# backplate.net
KiCad netlist of a schematic drawn in EAGLE
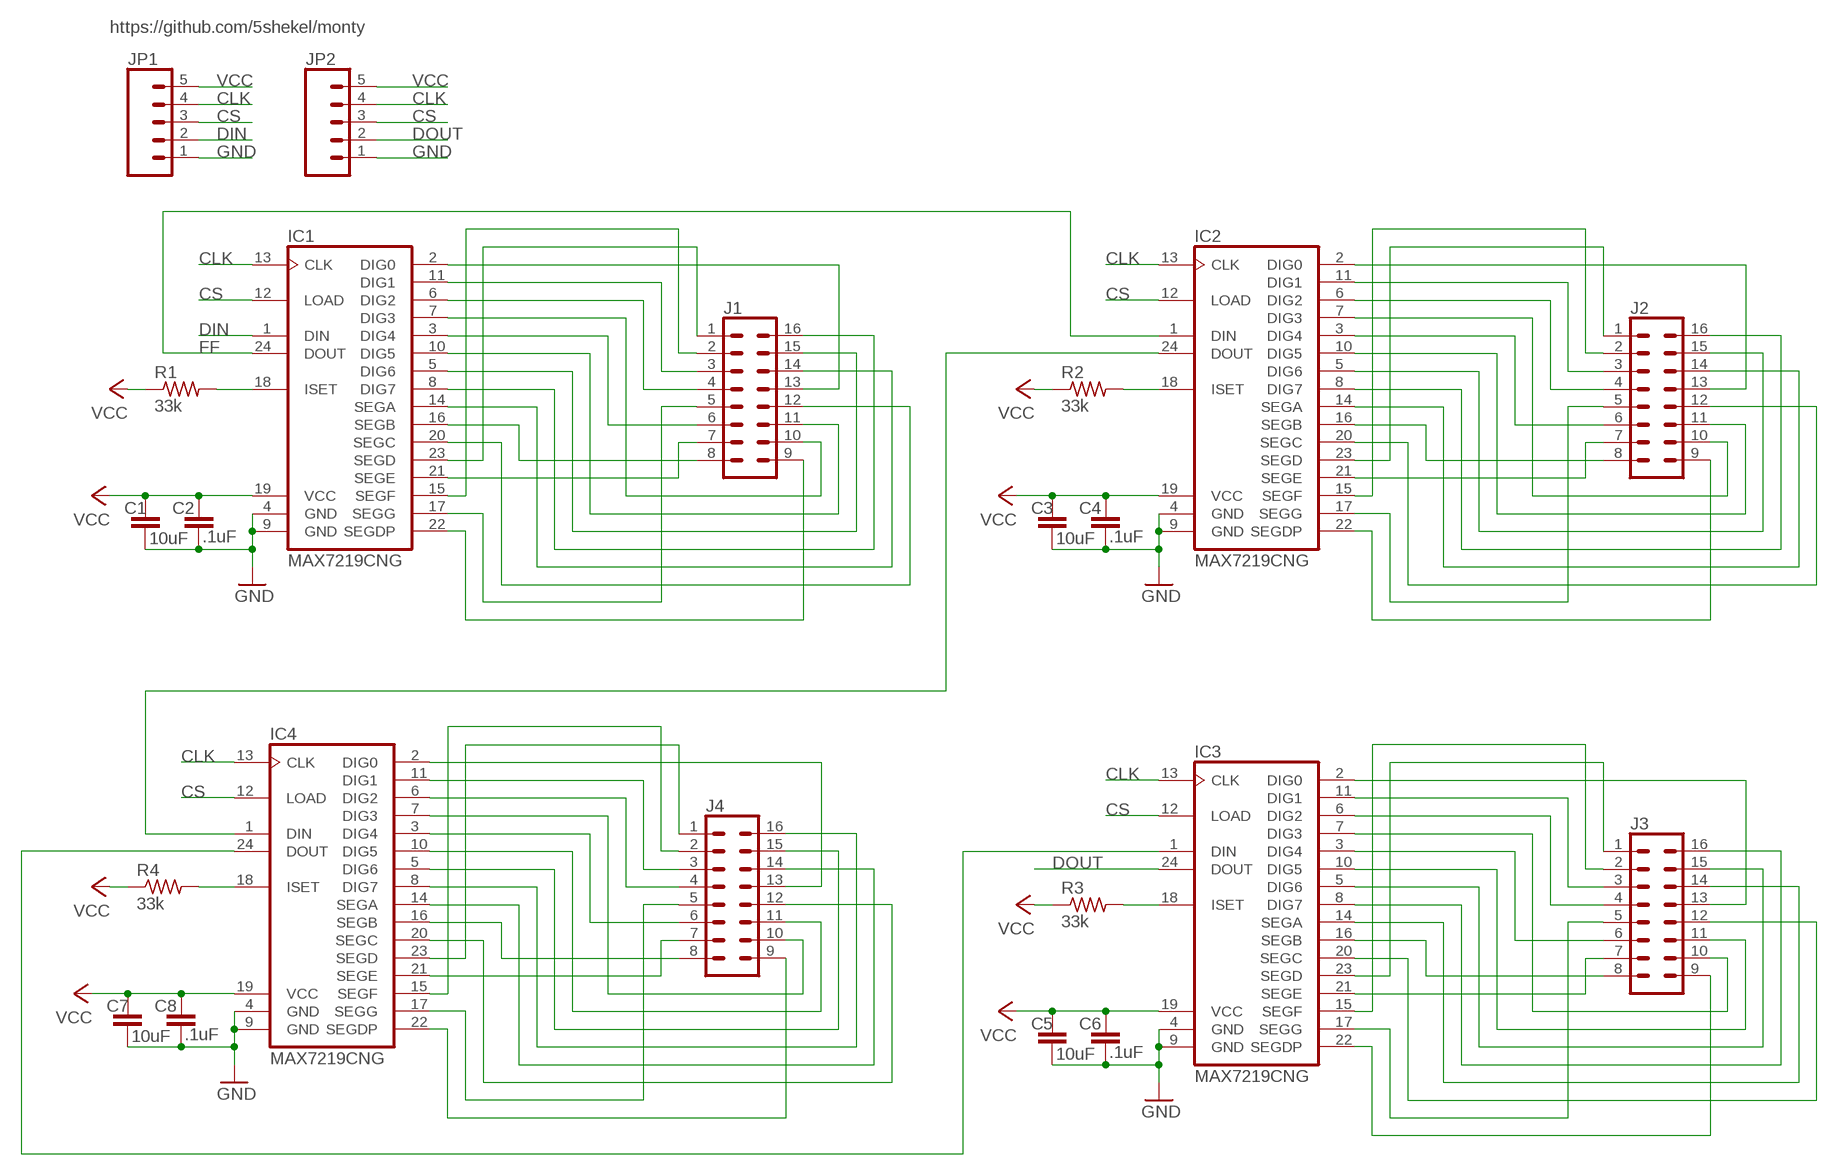
[diagram p0: schematic, sheet 1]

(export (version "E")
  (design (tool "Eeschema 10.0.6"))
  (components
    (comp (ref "C1")
      (value "10uF")
      (footprint "eagle-import:0805")
      (libsource (lib "eagle-import") (part "CAP0805"))
    )
    (comp (ref "C2")
      (value ".1uF")
      (footprint "eagle-import:0805")
      (libsource (lib "eagle-import") (part "CAP0805"))
    )
    (comp (ref "C3")
      (value "10uF")
      (footprint "eagle-import:0805")
      (libsource (lib "eagle-import") (part "CAP0805"))
    )
    (comp (ref "C4")
      (value ".1uF")
      (footprint "eagle-import:0805")
      (libsource (lib "eagle-import") (part "CAP0805"))
    )
    (comp (ref "C5")
      (value "10uF")
      (footprint "eagle-import:0805")
      (libsource (lib "eagle-import") (part "CAP0805"))
    )
    (comp (ref "C6")
      (value ".1uF")
      (footprint "eagle-import:0805")
      (libsource (lib "eagle-import") (part "CAP0805"))
    )
    (comp (ref "C7")
      (value "10uF")
      (footprint "eagle-import:0805")
      (libsource (lib "eagle-import") (part "CAP0805"))
    )
    (comp (ref "C8")
      (value ".1uF")
      (footprint "eagle-import:0805")
      (libsource (lib "eagle-import") (part "CAP0805"))
    )
    (comp (ref "IC1")
      (value "MAX7219CNG")
      (footprint "eagle-import:DIL24-3")
      (fields (field (name "MF") "MAXIM"))
      (libsource (lib "eagle-import") (part "MAX7219CNG"))
    )
    (comp (ref "IC2")
      (value "MAX7219CNG")
      (footprint "eagle-import:DIL24-3")
      (fields (field (name "MF") "MAXIM"))
      (libsource (lib "eagle-import") (part "MAX7219CNG"))
    )
    (comp (ref "IC3")
      (value "MAX7219CNG")
      (footprint "eagle-import:DIL24-3")
      (fields (field (name "MF") "MAXIM"))
      (libsource (lib "eagle-import") (part "MAX7219CNG"))
    )
    (comp (ref "IC4")
      (value "MAX7219CNG")
      (footprint "eagle-import:DIL24-3")
      (fields (field (name "MF") "MAXIM"))
      (libsource (lib "eagle-import") (part "MAX7219CNG"))
    )
    (comp (ref "J1")
      (value "CONN_08X2IC")
      (footprint "eagle-import:2X8")
      (libsource (lib "eagle-import") (part "CONN_08X2IC"))
    )
    (comp (ref "J2")
      (value "CONN_08X2IC")
      (footprint "eagle-import:2X8")
      (libsource (lib "eagle-import") (part "CONN_08X2IC"))
    )
    (comp (ref "J3")
      (value "CONN_08X2IC")
      (footprint "eagle-import:2X8")
      (libsource (lib "eagle-import") (part "CONN_08X2IC"))
    )
    (comp (ref "J4")
      (value "CONN_08X2IC")
      (footprint "eagle-import:2X8")
      (libsource (lib "eagle-import") (part "CONN_08X2IC"))
    )
    (comp (ref "JP1")
      (value "CONN_05")
      (footprint "eagle-import:1X05")
      (libsource (lib "eagle-import") (part "CONN_05"))
    )
    (comp (ref "JP2")
      (value "CONN_05")
      (footprint "eagle-import:1X05")
      (libsource (lib "eagle-import") (part "CONN_05"))
    )
    (comp (ref "R1")
      (value "33k")
      (footprint "eagle-import:V526-0")
      (libsource (lib "eagle-import") (part "R-US_V526-0"))
    )
    (comp (ref "R2")
      (value "33k")
      (footprint "eagle-import:V526-0")
      (libsource (lib "eagle-import") (part "R-US_V526-0"))
    )
    (comp (ref "R3")
      (value "33k")
      (footprint "eagle-import:V526-0")
      (libsource (lib "eagle-import") (part "R-US_V526-0"))
    )
    (comp (ref "R4")
      (value "33k")
      (footprint "eagle-import:V526-0")
      (libsource (lib "eagle-import") (part "R-US_V526-0"))
    )
  )
  (nets
    (net (code "1") (name "/CLK") (class "Default")
      (node (ref "IC1") (pin "13") (pinfunction "CLK_13") (pintype "input"))
      (node (ref "IC2") (pin "13") (pinfunction "CLK_13") (pintype "input"))
      (node (ref "IC3") (pin "13") (pinfunction "CLK_13") (pintype "input"))
      (node (ref "IC4") (pin "13") (pinfunction "CLK_13") (pintype "input"))
      (node (ref "JP1") (pin "4") (pinfunction "4_4") (pintype "passive"))
      (node (ref "JP2") (pin "4") (pinfunction "4_4") (pintype "passive"))
    )
    (net (code "2") (name "/CS") (class "Default")
      (node (ref "IC1") (pin "12") (pinfunction "LOAD_12") (pintype "input"))
      (node (ref "IC2") (pin "12") (pinfunction "LOAD_12") (pintype "input"))
      (node (ref "IC3") (pin "12") (pinfunction "LOAD_12") (pintype "input"))
      (node (ref "IC4") (pin "12") (pinfunction "LOAD_12") (pintype "input"))
      (node (ref "JP1") (pin "3") (pinfunction "3_3") (pintype "passive"))
      (node (ref "JP2") (pin "3") (pinfunction "3_3") (pintype "passive"))
    )
    (net (code "3") (name "/DIN") (class "Default")
      (node (ref "IC1") (pin "1") (pinfunction "DIN_1") (pintype "input"))
      (node (ref "JP1") (pin "2") (pinfunction "2_2") (pintype "passive"))
    )
    (net (code "4") (name "/DOUT") (class "Default")
      (node (ref "IC3") (pin "24") (pinfunction "DOUT_24") (pintype "output"))
      (node (ref "JP2") (pin "2") (pinfunction "2_2") (pintype "passive"))
    )
    (net (code "5") (name "/FF") (class "Default")
      (node (ref "IC1") (pin "24") (pinfunction "DOUT_24") (pintype "output"))
      (node (ref "IC2") (pin "1") (pinfunction "DIN_1") (pintype "input"))
    )
    (net (code "6") (name "GND") (class "Default")
      (node (ref "C1") (pin "2") (pinfunction "2_2") (pintype "passive"))
      (node (ref "C2") (pin "2") (pinfunction "2_2") (pintype "passive"))
      (node (ref "C3") (pin "2") (pinfunction "2_2") (pintype "passive"))
      (node (ref "C4") (pin "2") (pinfunction "2_2") (pintype "passive"))
      (node (ref "C5") (pin "2") (pinfunction "2_2") (pintype "passive"))
      (node (ref "C6") (pin "2") (pinfunction "2_2") (pintype "passive"))
      (node (ref "C7") (pin "2") (pinfunction "2_2") (pintype "passive"))
      (node (ref "C8") (pin "2") (pinfunction "2_2") (pintype "passive"))
      (node (ref "IC1") (pin "4") (pinfunction "GND_4") (pintype "power_in"))
      (node (ref "IC1") (pin "9") (pinfunction "GND_9") (pintype "power_in"))
      (node (ref "IC2") (pin "4") (pinfunction "GND_4") (pintype "power_in"))
      (node (ref "IC2") (pin "9") (pinfunction "GND_9") (pintype "power_in"))
      (node (ref "IC3") (pin "4") (pinfunction "GND_4") (pintype "power_in"))
      (node (ref "IC3") (pin "9") (pinfunction "GND_9") (pintype "power_in"))
      (node (ref "IC4") (pin "4") (pinfunction "GND_4") (pintype "power_in"))
      (node (ref "IC4") (pin "9") (pinfunction "GND_9") (pintype "power_in"))
      (node (ref "JP1") (pin "1") (pinfunction "1_1") (pintype "passive"))
      (node (ref "JP2") (pin "1") (pinfunction "1_1") (pintype "passive"))
    )
    (net (code "7") (name "Net-(IC1-DIG0)") (class "Default")
      (node (ref "IC1") (pin "2") (pinfunction "DIG0_2") (pintype "output"))
      (node (ref "J1") (pin "13") (pinfunction "8_13") (pintype "passive"))
    )
    (net (code "8") (name "Net-(IC1-DIG1)") (class "Default")
      (node (ref "IC1") (pin "11") (pinfunction "DIG1_11") (pintype "output"))
      (node (ref "J1") (pin "3") (pinfunction "5_3") (pintype "passive"))
    )
    (net (code "9") (name "Net-(IC1-DIG2)") (class "Default")
      (node (ref "IC1") (pin "6") (pinfunction "DIG2_6") (pintype "output"))
      (node (ref "J1") (pin "4") (pinfunction "7_4") (pintype "passive"))
    )
    (net (code "10") (name "Net-(IC1-DIG3)") (class "Default")
      (node (ref "IC1") (pin "7") (pinfunction "DIG3_7") (pintype "output"))
      (node (ref "J1") (pin "10") (pinfunction "14_10") (pintype "passive"))
    )
    (net (code "11") (name "Net-(IC1-DIG4)") (class "Default")
      (node (ref "IC1") (pin "3") (pinfunction "DIG4_3") (pintype "output"))
      (node (ref "J1") (pin "6") (pinfunction "11_6") (pintype "passive"))
    )
    (net (code "12") (name "Net-(IC1-DIG5)") (class "Default")
      (node (ref "IC1") (pin "10") (pinfunction "DIG5_10") (pintype "output"))
      (node (ref "J1") (pin "11") (pinfunction "12_11") (pintype "passive"))
    )
    (net (code "13") (name "Net-(IC1-DIG6)") (class "Default")
      (node (ref "IC1") (pin "5") (pinfunction "DIG6_5") (pintype "output"))
      (node (ref "J1") (pin "15") (pinfunction "4_15") (pintype "passive"))
    )
    (net (code "14") (name "Net-(IC1-DIG7)") (class "Default")
      (node (ref "IC1") (pin "8") (pinfunction "DIG7_8") (pintype "output"))
      (node (ref "J1") (pin "16") (pinfunction "2_16") (pintype "passive"))
    )
    (net (code "15") (name "Net-(IC1-ISET)") (class "Default")
      (node (ref "IC1") (pin "18") (pinfunction "ISET_18") (pintype "input"))
      (node (ref "R1") (pin "2") (pinfunction "2_2") (pintype "passive"))
    )
    (net (code "16") (name "Net-(IC1-SEGA)") (class "Default")
      (node (ref "IC1") (pin "14") (pinfunction "SEGA_14") (pintype "output"))
      (node (ref "J1") (pin "14") (pinfunction "6_14") (pintype "passive"))
    )
    (net (code "17") (name "Net-(IC1-SEGB)") (class "Default")
      (node (ref "IC1") (pin "16") (pinfunction "SEGB_16") (pintype "output"))
      (node (ref "J1") (pin "8") (pinfunction "15_8") (pintype "passive"))
    )
    (net (code "18") (name "Net-(IC1-SEGC)") (class "Default")
      (node (ref "IC1") (pin "20") (pinfunction "SEGC_20") (pintype "output"))
      (node (ref "J1") (pin "12") (pinfunction "10_12") (pintype "passive"))
    )
    (net (code "19") (name "Net-(IC1-SEGD)") (class "Default")
      (node (ref "IC1") (pin "23") (pinfunction "SEGD_23") (pintype "output"))
      (node (ref "J1") (pin "1") (pinfunction "1_1") (pintype "passive"))
    )
    (net (code "20") (name "Net-(IC1-SEGDP)") (class "Default")
      (node (ref "IC1") (pin "22") (pinfunction "SEGDP_22") (pintype "output"))
      (node (ref "J1") (pin "9") (pinfunction "16_9") (pintype "passive"))
    )
    (net (code "21") (name "Net-(IC1-SEGE)") (class "Default")
      (node (ref "IC1") (pin "21") (pinfunction "SEGE_21") (pintype "output"))
      (node (ref "J1") (pin "7") (pinfunction "13_7") (pintype "passive"))
    )
    (net (code "22") (name "Net-(IC1-SEGF)") (class "Default")
      (node (ref "IC1") (pin "15") (pinfunction "SEGF_15") (pintype "output"))
      (node (ref "J1") (pin "2") (pinfunction "3_2") (pintype "passive"))
    )
    (net (code "23") (name "Net-(IC1-SEGG)") (class "Default")
      (node (ref "IC1") (pin "17") (pinfunction "SEGG_17") (pintype "output"))
      (node (ref "J1") (pin "5") (pinfunction "9_5") (pintype "passive"))
    )
    (net (code "24") (name "Net-(IC2-DIG0)") (class "Default")
      (node (ref "IC2") (pin "2") (pinfunction "DIG0_2") (pintype "output"))
      (node (ref "J2") (pin "13") (pinfunction "8_13") (pintype "passive"))
    )
    (net (code "25") (name "Net-(IC2-DIG1)") (class "Default")
      (node (ref "IC2") (pin "11") (pinfunction "DIG1_11") (pintype "output"))
      (node (ref "J2") (pin "3") (pinfunction "5_3") (pintype "passive"))
    )
    (net (code "26") (name "Net-(IC2-DIG2)") (class "Default")
      (node (ref "IC2") (pin "6") (pinfunction "DIG2_6") (pintype "output"))
      (node (ref "J2") (pin "4") (pinfunction "7_4") (pintype "passive"))
    )
    (net (code "27") (name "Net-(IC2-DIG3)") (class "Default")
      (node (ref "IC2") (pin "7") (pinfunction "DIG3_7") (pintype "output"))
      (node (ref "J2") (pin "10") (pinfunction "14_10") (pintype "passive"))
    )
    (net (code "28") (name "Net-(IC2-DIG4)") (class "Default")
      (node (ref "IC2") (pin "3") (pinfunction "DIG4_3") (pintype "output"))
      (node (ref "J2") (pin "6") (pinfunction "11_6") (pintype "passive"))
    )
    (net (code "29") (name "Net-(IC2-DIG5)") (class "Default")
      (node (ref "IC2") (pin "10") (pinfunction "DIG5_10") (pintype "output"))
      (node (ref "J2") (pin "11") (pinfunction "12_11") (pintype "passive"))
    )
    (net (code "30") (name "Net-(IC2-DIG6)") (class "Default")
      (node (ref "IC2") (pin "5") (pinfunction "DIG6_5") (pintype "output"))
      (node (ref "J2") (pin "15") (pinfunction "4_15") (pintype "passive"))
    )
    (net (code "31") (name "Net-(IC2-DIG7)") (class "Default")
      (node (ref "IC2") (pin "8") (pinfunction "DIG7_8") (pintype "output"))
      (node (ref "J2") (pin "16") (pinfunction "2_16") (pintype "passive"))
    )
    (net (code "32") (name "Net-(IC2-DOUT)") (class "Default")
      (node (ref "IC2") (pin "24") (pinfunction "DOUT_24") (pintype "output"))
      (node (ref "IC4") (pin "1") (pinfunction "DIN_1") (pintype "input"))
    )
    (net (code "33") (name "Net-(IC2-ISET)") (class "Default")
      (node (ref "IC2") (pin "18") (pinfunction "ISET_18") (pintype "input"))
      (node (ref "R2") (pin "2") (pinfunction "2_2") (pintype "passive"))
    )
    (net (code "34") (name "Net-(IC2-SEGA)") (class "Default")
      (node (ref "IC2") (pin "14") (pinfunction "SEGA_14") (pintype "output"))
      (node (ref "J2") (pin "14") (pinfunction "6_14") (pintype "passive"))
    )
    (net (code "35") (name "Net-(IC2-SEGB)") (class "Default")
      (node (ref "IC2") (pin "16") (pinfunction "SEGB_16") (pintype "output"))
      (node (ref "J2") (pin "8") (pinfunction "15_8") (pintype "passive"))
    )
    (net (code "36") (name "Net-(IC2-SEGC)") (class "Default")
      (node (ref "IC2") (pin "20") (pinfunction "SEGC_20") (pintype "output"))
      (node (ref "J2") (pin "12") (pinfunction "10_12") (pintype "passive"))
    )
    (net (code "37") (name "Net-(IC2-SEGD)") (class "Default")
      (node (ref "IC2") (pin "23") (pinfunction "SEGD_23") (pintype "output"))
      (node (ref "J2") (pin "1") (pinfunction "1_1") (pintype "passive"))
    )
    (net (code "38") (name "Net-(IC2-SEGDP)") (class "Default")
      (node (ref "IC2") (pin "22") (pinfunction "SEGDP_22") (pintype "output"))
      (node (ref "J2") (pin "9") (pinfunction "16_9") (pintype "passive"))
    )
    (net (code "39") (name "Net-(IC2-SEGE)") (class "Default")
      (node (ref "IC2") (pin "21") (pinfunction "SEGE_21") (pintype "output"))
      (node (ref "J2") (pin "7") (pinfunction "13_7") (pintype "passive"))
    )
    (net (code "40") (name "Net-(IC2-SEGF)") (class "Default")
      (node (ref "IC2") (pin "15") (pinfunction "SEGF_15") (pintype "output"))
      (node (ref "J2") (pin "2") (pinfunction "3_2") (pintype "passive"))
    )
    (net (code "41") (name "Net-(IC2-SEGG)") (class "Default")
      (node (ref "IC2") (pin "17") (pinfunction "SEGG_17") (pintype "output"))
      (node (ref "J2") (pin "5") (pinfunction "9_5") (pintype "passive"))
    )
    (net (code "42") (name "Net-(IC3-DIG0)") (class "Default")
      (node (ref "IC3") (pin "2") (pinfunction "DIG0_2") (pintype "output"))
      (node (ref "J3") (pin "13") (pinfunction "8_13") (pintype "passive"))
    )
    (net (code "43") (name "Net-(IC3-DIG1)") (class "Default")
      (node (ref "IC3") (pin "11") (pinfunction "DIG1_11") (pintype "output"))
      (node (ref "J3") (pin "3") (pinfunction "5_3") (pintype "passive"))
    )
    (net (code "44") (name "Net-(IC3-DIG2)") (class "Default")
      (node (ref "IC3") (pin "6") (pinfunction "DIG2_6") (pintype "output"))
      (node (ref "J3") (pin "4") (pinfunction "7_4") (pintype "passive"))
    )
    (net (code "45") (name "Net-(IC3-DIG3)") (class "Default")
      (node (ref "IC3") (pin "7") (pinfunction "DIG3_7") (pintype "output"))
      (node (ref "J3") (pin "10") (pinfunction "14_10") (pintype "passive"))
    )
    (net (code "46") (name "Net-(IC3-DIG4)") (class "Default")
      (node (ref "IC3") (pin "3") (pinfunction "DIG4_3") (pintype "output"))
      (node (ref "J3") (pin "6") (pinfunction "11_6") (pintype "passive"))
    )
    (net (code "47") (name "Net-(IC3-DIG5)") (class "Default")
      (node (ref "IC3") (pin "10") (pinfunction "DIG5_10") (pintype "output"))
      (node (ref "J3") (pin "11") (pinfunction "12_11") (pintype "passive"))
    )
    (net (code "48") (name "Net-(IC3-DIG6)") (class "Default")
      (node (ref "IC3") (pin "5") (pinfunction "DIG6_5") (pintype "output"))
      (node (ref "J3") (pin "15") (pinfunction "4_15") (pintype "passive"))
    )
    (net (code "49") (name "Net-(IC3-DIG7)") (class "Default")
      (node (ref "IC3") (pin "8") (pinfunction "DIG7_8") (pintype "output"))
      (node (ref "J3") (pin "16") (pinfunction "2_16") (pintype "passive"))
    )
    (net (code "50") (name "Net-(IC3-DIN)") (class "Default")
      (node (ref "IC3") (pin "1") (pinfunction "DIN_1") (pintype "input"))
      (node (ref "IC4") (pin "24") (pinfunction "DOUT_24") (pintype "output"))
    )
    (net (code "51") (name "Net-(IC3-ISET)") (class "Default")
      (node (ref "IC3") (pin "18") (pinfunction "ISET_18") (pintype "input"))
      (node (ref "R3") (pin "2") (pinfunction "2_2") (pintype "passive"))
    )
    (net (code "52") (name "Net-(IC3-SEGA)") (class "Default")
      (node (ref "IC3") (pin "14") (pinfunction "SEGA_14") (pintype "output"))
      (node (ref "J3") (pin "14") (pinfunction "6_14") (pintype "passive"))
    )
    (net (code "53") (name "Net-(IC3-SEGB)") (class "Default")
      (node (ref "IC3") (pin "16") (pinfunction "SEGB_16") (pintype "output"))
      (node (ref "J3") (pin "8") (pinfunction "15_8") (pintype "passive"))
    )
    (net (code "54") (name "Net-(IC3-SEGC)") (class "Default")
      (node (ref "IC3") (pin "20") (pinfunction "SEGC_20") (pintype "output"))
      (node (ref "J3") (pin "12") (pinfunction "10_12") (pintype "passive"))
    )
    (net (code "55") (name "Net-(IC3-SEGD)") (class "Default")
      (node (ref "IC3") (pin "23") (pinfunction "SEGD_23") (pintype "output"))
      (node (ref "J3") (pin "1") (pinfunction "1_1") (pintype "passive"))
    )
    (net (code "56") (name "Net-(IC3-SEGDP)") (class "Default")
      (node (ref "IC3") (pin "22") (pinfunction "SEGDP_22") (pintype "output"))
      (node (ref "J3") (pin "9") (pinfunction "16_9") (pintype "passive"))
    )
    (net (code "57") (name "Net-(IC3-SEGE)") (class "Default")
      (node (ref "IC3") (pin "21") (pinfunction "SEGE_21") (pintype "output"))
      (node (ref "J3") (pin "7") (pinfunction "13_7") (pintype "passive"))
    )
    (net (code "58") (name "Net-(IC3-SEGF)") (class "Default")
      (node (ref "IC3") (pin "15") (pinfunction "SEGF_15") (pintype "output"))
      (node (ref "J3") (pin "2") (pinfunction "3_2") (pintype "passive"))
    )
    (net (code "59") (name "Net-(IC3-SEGG)") (class "Default")
      (node (ref "IC3") (pin "17") (pinfunction "SEGG_17") (pintype "output"))
      (node (ref "J3") (pin "5") (pinfunction "9_5") (pintype "passive"))
    )
    (net (code "60") (name "Net-(IC4-DIG0)") (class "Default")
      (node (ref "IC4") (pin "2") (pinfunction "DIG0_2") (pintype "output"))
      (node (ref "J4") (pin "13") (pinfunction "8_13") (pintype "passive"))
    )
    (net (code "61") (name "Net-(IC4-DIG1)") (class "Default")
      (node (ref "IC4") (pin "11") (pinfunction "DIG1_11") (pintype "output"))
      (node (ref "J4") (pin "3") (pinfunction "5_3") (pintype "passive"))
    )
    (net (code "62") (name "Net-(IC4-DIG2)") (class "Default")
      (node (ref "IC4") (pin "6") (pinfunction "DIG2_6") (pintype "output"))
      (node (ref "J4") (pin "4") (pinfunction "7_4") (pintype "passive"))
    )
    (net (code "63") (name "Net-(IC4-DIG3)") (class "Default")
      (node (ref "IC4") (pin "7") (pinfunction "DIG3_7") (pintype "output"))
      (node (ref "J4") (pin "10") (pinfunction "14_10") (pintype "passive"))
    )
    (net (code "64") (name "Net-(IC4-DIG4)") (class "Default")
      (node (ref "IC4") (pin "3") (pinfunction "DIG4_3") (pintype "output"))
      (node (ref "J4") (pin "6") (pinfunction "11_6") (pintype "passive"))
    )
    (net (code "65") (name "Net-(IC4-DIG5)") (class "Default")
      (node (ref "IC4") (pin "10") (pinfunction "DIG5_10") (pintype "output"))
      (node (ref "J4") (pin "11") (pinfunction "12_11") (pintype "passive"))
    )
    (net (code "66") (name "Net-(IC4-DIG6)") (class "Default")
      (node (ref "IC4") (pin "5") (pinfunction "DIG6_5") (pintype "output"))
      (node (ref "J4") (pin "15") (pinfunction "4_15") (pintype "passive"))
    )
    (net (code "67") (name "Net-(IC4-DIG7)") (class "Default")
      (node (ref "IC4") (pin "8") (pinfunction "DIG7_8") (pintype "output"))
      (node (ref "J4") (pin "16") (pinfunction "2_16") (pintype "passive"))
    )
    (net (code "68") (name "Net-(IC4-ISET)") (class "Default")
      (node (ref "IC4") (pin "18") (pinfunction "ISET_18") (pintype "input"))
      (node (ref "R4") (pin "2") (pinfunction "2_2") (pintype "passive"))
    )
    (net (code "69") (name "Net-(IC4-SEGA)") (class "Default")
      (node (ref "IC4") (pin "14") (pinfunction "SEGA_14") (pintype "output"))
      (node (ref "J4") (pin "14") (pinfunction "6_14") (pintype "passive"))
    )
    (net (code "70") (name "Net-(IC4-SEGB)") (class "Default")
      (node (ref "IC4") (pin "16") (pinfunction "SEGB_16") (pintype "output"))
      (node (ref "J4") (pin "8") (pinfunction "15_8") (pintype "passive"))
    )
    (net (code "71") (name "Net-(IC4-SEGC)") (class "Default")
      (node (ref "IC4") (pin "20") (pinfunction "SEGC_20") (pintype "output"))
      (node (ref "J4") (pin "12") (pinfunction "10_12") (pintype "passive"))
    )
    (net (code "72") (name "Net-(IC4-SEGD)") (class "Default")
      (node (ref "IC4") (pin "23") (pinfunction "SEGD_23") (pintype "output"))
      (node (ref "J4") (pin "1") (pinfunction "1_1") (pintype "passive"))
    )
    (net (code "73") (name "Net-(IC4-SEGDP)") (class "Default")
      (node (ref "IC4") (pin "22") (pinfunction "SEGDP_22") (pintype "output"))
      (node (ref "J4") (pin "9") (pinfunction "16_9") (pintype "passive"))
    )
    (net (code "74") (name "Net-(IC4-SEGE)") (class "Default")
      (node (ref "IC4") (pin "21") (pinfunction "SEGE_21") (pintype "output"))
      (node (ref "J4") (pin "7") (pinfunction "13_7") (pintype "passive"))
    )
    (net (code "75") (name "Net-(IC4-SEGF)") (class "Default")
      (node (ref "IC4") (pin "15") (pinfunction "SEGF_15") (pintype "output"))
      (node (ref "J4") (pin "2") (pinfunction "3_2") (pintype "passive"))
    )
    (net (code "76") (name "Net-(IC4-SEGG)") (class "Default")
      (node (ref "IC4") (pin "17") (pinfunction "SEGG_17") (pintype "output"))
      (node (ref "J4") (pin "5") (pinfunction "9_5") (pintype "passive"))
    )
    (net (code "77") (name "VCC") (class "Default")
      (node (ref "C1") (pin "1") (pinfunction "1_1") (pintype "passive"))
      (node (ref "C2") (pin "1") (pinfunction "1_1") (pintype "passive"))
      (node (ref "C3") (pin "1") (pinfunction "1_1") (pintype "passive"))
      (node (ref "C4") (pin "1") (pinfunction "1_1") (pintype "passive"))
      (node (ref "C5") (pin "1") (pinfunction "1_1") (pintype "passive"))
      (node (ref "C6") (pin "1") (pinfunction "1_1") (pintype "passive"))
      (node (ref "C7") (pin "1") (pinfunction "1_1") (pintype "passive"))
      (node (ref "C8") (pin "1") (pinfunction "1_1") (pintype "passive"))
      (node (ref "IC1") (pin "19") (pinfunction "VCC_19") (pintype "power_in"))
      (node (ref "IC2") (pin "19") (pinfunction "VCC_19") (pintype "power_in"))
      (node (ref "IC3") (pin "19") (pinfunction "VCC_19") (pintype "power_in"))
      (node (ref "IC4") (pin "19") (pinfunction "VCC_19") (pintype "power_in"))
      (node (ref "JP1") (pin "5") (pinfunction "5_5") (pintype "passive"))
      (node (ref "JP2") (pin "5") (pinfunction "5_5") (pintype "passive"))
      (node (ref "R1") (pin "1") (pinfunction "1_1") (pintype "passive"))
      (node (ref "R2") (pin "1") (pinfunction "1_1") (pintype "passive"))
      (node (ref "R3") (pin "1") (pinfunction "1_1") (pintype "passive"))
      (node (ref "R4") (pin "1") (pinfunction "1_1") (pintype "passive"))
    )
  )
)
